# Sheet1.net
KiCad netlist of a schematic drawn in Altium Designer
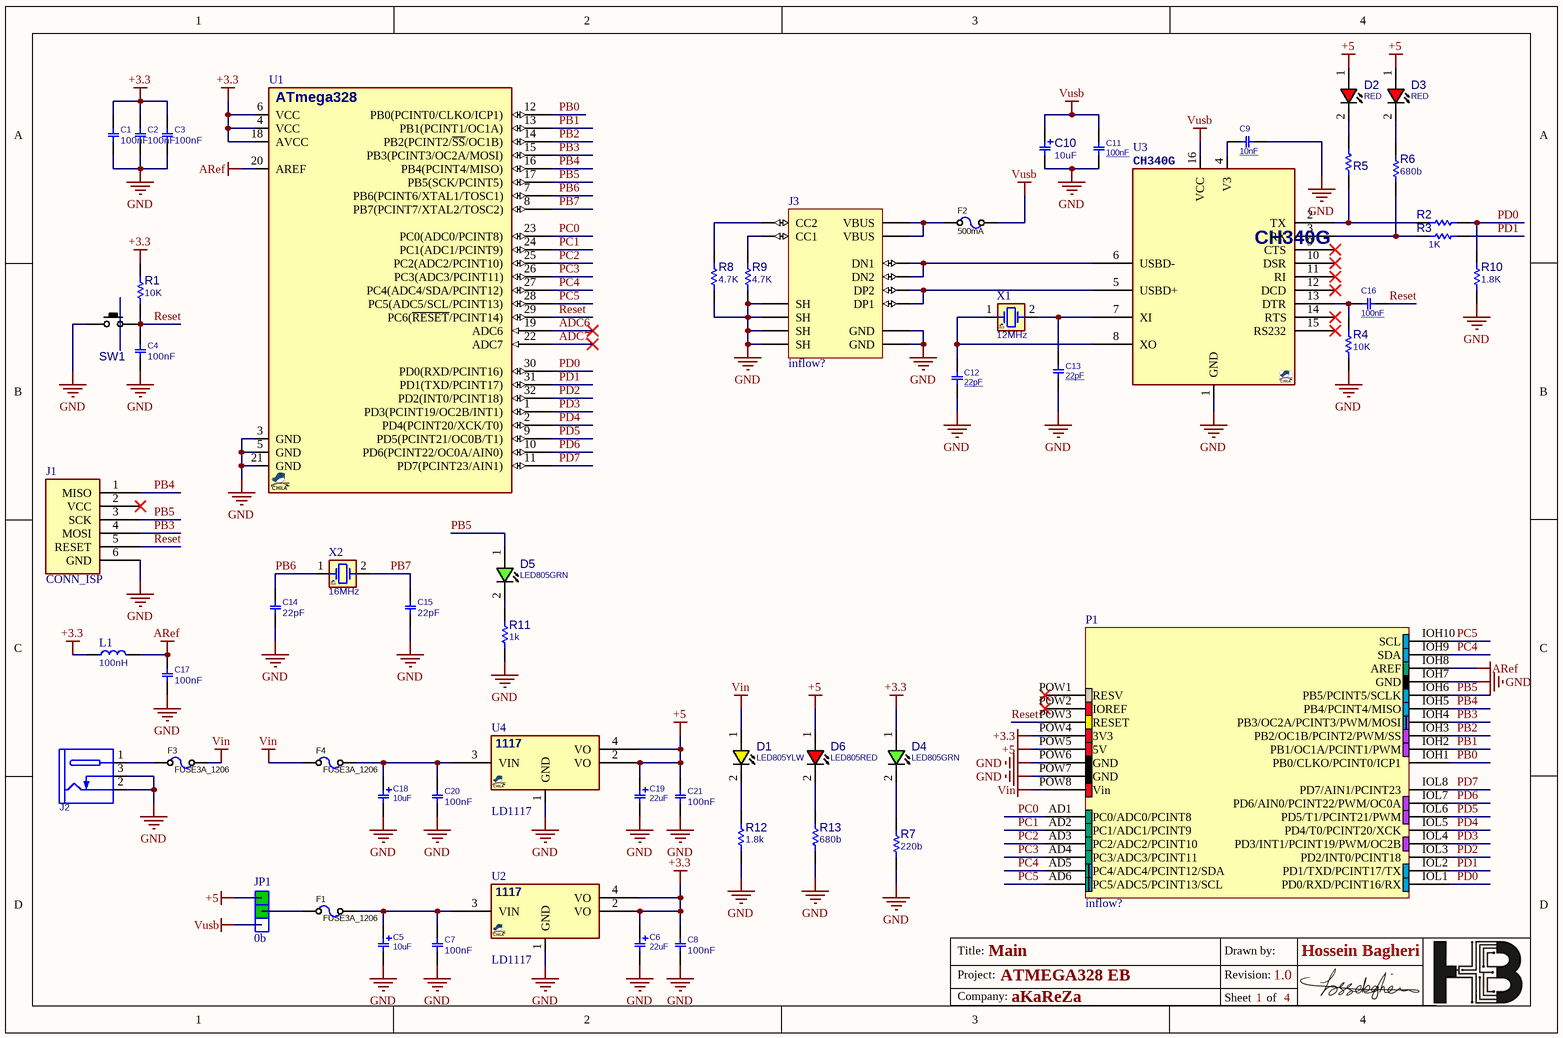
[diagram p0: Sheet1.SchDoc]

(export (version "E")
  (design (tool "Eeschema 10.0.6"))
  (components
    (comp (ref "C1")
      (value "100nF")
      (footprint "C0805")
      (description "CAP, MLCC")
      (fields (field (name "MANF_P#") "MANF_PART#"))
      (libsource (lib "Chila_PCB") (part "CAP_SMD_MLCC_0805"))
    )
    (comp (ref "C2")
      (value "100nF")
      (footprint "C0805")
      (description "CAP, MLCC")
      (fields (field (name "MANF_P#") "MANF_PART#"))
      (libsource (lib "Chila_PCB") (part "CAP_SMD_MLCC_0805"))
    )
    (comp (ref "C3")
      (value "100nF")
      (footprint "C0805")
      (description "CAP, MLCC")
      (fields (field (name "MANF_P#") "MANF_PART#"))
      (libsource (lib "Chila_PCB") (part "CAP_SMD_MLCC_0805"))
    )
    (comp (ref "C4")
      (value "100nF")
      (footprint "C0805")
      (description "CAP, MLCC")
      (fields (field (name "MANF_P#") "MANF_PART#"))
      (libsource (lib "Chila_PCB") (part "CAP_SMD_MLCC_0805"))
    )
    (comp (ref "C5")
      (value "10uF")
      (footprint "C_TN_2012")
      (description "CAP, SMD, TAN")
      (fields (field (name "MANF") "VISHAY") (field (name "MANF_P#") "T55A106M6R3C0300"))
      (libsource (lib "Chila_PCB") (part "CAP_SMD_TAN"))
    )
    (comp (ref "C6")
      (value "22uF")
      (footprint "C_TN_2012")
      (description "CAP, SMD, TAN")
      (fields (field (name "MANF") "VISHAY") (field (name "MANF_P#") "T55A106M6R3C0300"))
      (libsource (lib "Chila_PCB") (part "CAP_SMD_TAN"))
    )
    (comp (ref "C7")
      (value "100nF")
      (footprint "C1206")
      (description "CAP, MLCC")
      (fields (field (name "MANF_P#") "MANF_PART#"))
      (libsource (lib "Chila_PCB") (part "CAP_SMD_MLCC_1206"))
    )
    (comp (ref "C8")
      (value "100nF")
      (footprint "C1206")
      (description "CAP, MLCC")
      (fields (field (name "MANF_P#") "MANF_PART#"))
      (libsource (lib "Chila_PCB") (part "CAP_SMD_MLCC_1206"))
    )
    (comp (ref "C9")
      (value "10nF")
      (footprint "C1206")
      (description "CAP, FILM, 680nF, 16V, Acryl, 20%, 1206")
      (fields (field (name "MANF") "Murata"))
      (libsource (lib "Chila_PCB") (part "CAP_SMD_FILM"))
    )
    (comp (ref "C10")
      (value "10uF")
      (footprint "C_EL_D4L5")
      (description "CAP, SMD, ELEC,")
      (fields (field (name "MANF_P#") "MANF_PART#") (field (name "MANF") "MANF"))
      (libsource (lib "Chila_PCB") (part "CAP_SMD_EL"))
    )
    (comp (ref "C11")
      (value "100nF")
      (footprint "C1206")
      (description "CAP, FILM, 680nF, 16V, Acryl, 20%, 1206")
      (fields (field (name "MANF") "Murata"))
      (libsource (lib "Chila_PCB") (part "CAP_SMD_FILM"))
    )
    (comp (ref "C12")
      (value "22pF")
      (footprint "C1206")
      (description "CAP, FILM, 680nF, 16V, Acryl, 20%, 1206")
      (fields (field (name "MANF") "Murata"))
      (libsource (lib "Chila_PCB") (part "CAP_SMD_FILM"))
    )
    (comp (ref "C13")
      (value "22pF")
      (footprint "C1206")
      (description "CAP, FILM, 680nF, 16V, Acryl, 20%, 1206")
      (fields (field (name "MANF") "Murata"))
      (libsource (lib "Chila_PCB") (part "CAP_SMD_FILM"))
    )
    (comp (ref "C14")
      (value "22pF")
      (footprint "C0805")
      (description "CAP, MLCC")
      (fields (field (name "MANF_P#") "MANF_PART#"))
      (libsource (lib "Chila_PCB") (part "CAP_SMD_MLCC_0805"))
    )
    (comp (ref "C15")
      (value "22pF")
      (footprint "C0805")
      (description "CAP, MLCC")
      (fields (field (name "MANF_P#") "MANF_PART#"))
      (libsource (lib "Chila_PCB") (part "CAP_SMD_MLCC_0805"))
    )
    (comp (ref "C16")
      (value "100nF")
      (footprint "C1206")
      (description "CAP, FILM, 680nF, 16V, Acryl, 20%, 1206")
      (fields (field (name "MANF") "Murata"))
      (libsource (lib "Chila_PCB") (part "CAP_SMD_FILM"))
    )
    (comp (ref "C17")
      (value "100nF")
      (footprint "C0805")
      (description "CAP, MLCC")
      (fields (field (name "MANF_P#") "MANF_PART#"))
      (libsource (lib "Chila_PCB") (part "CAP_SMD_MLCC_0805"))
    )
    (comp (ref "C18")
      (value "10uF")
      (footprint "C_TN_2012")
      (description "CAP, SMD, TAN")
      (fields (field (name "MANF") "VISHAY") (field (name "MANF_P#") "T55A106M6R3C0300"))
      (libsource (lib "Chila_PCB") (part "CAP_SMD_TAN"))
    )
    (comp (ref "C19")
      (value "22uF")
      (footprint "C_TN_2012")
      (description "CAP, SMD, TAN")
      (fields (field (name "MANF") "VISHAY") (field (name "MANF_P#") "T55A106M6R3C0300"))
      (libsource (lib "Chila_PCB") (part "CAP_SMD_TAN"))
    )
    (comp (ref "C20")
      (value "100nF")
      (footprint "C1206")
      (description "CAP, MLCC")
      (fields (field (name "MANF_P#") "MANF_PART#"))
      (libsource (lib "Chila_PCB") (part "CAP_SMD_MLCC_1206"))
    )
    (comp (ref "C21")
      (value "100nF")
      (footprint "C1206")
      (description "CAP, MLCC")
      (fields (field (name "MANF_P#") "MANF_PART#"))
      (libsource (lib "Chila_PCB") (part "CAP_SMD_MLCC_1206"))
    )
    (comp (ref "D1")
      (value "LED805YLW")
      (footprint "LED0805YLW")
      (description "LED, SMD, 0805, YELLOW")
      (fields (field (name "MANF") "MANF") (field (name "MANF_P#") "MANF_PART#"))
      (libsource (lib "Chila_PCB") (part "LED_SMD_0805_YLW"))
    )
    (comp (ref "D2")
      (value "RED")
      (footprint "LED0805RED")
      (description "LED, SMD, 0805, RED")
      (fields (field (name "MANF") "MANF") (field (name "MANF_P#") "MANF_PART#"))
      (libsource (lib "Chila_PCB") (part "LED_SMD_0805_RED"))
    )
    (comp (ref "D3")
      (value "RED")
      (footprint "LED0805RED")
      (description "LED, SMD, 0805, RED")
      (fields (field (name "MANF") "MANF") (field (name "MANF_P#") "MANF_PART#"))
      (libsource (lib "Chila_PCB") (part "LED_SMD_0805_RED"))
    )
    (comp (ref "D4")
      (value "LED805GRN")
      (footprint "LED0805GRN")
      (description "LED, SMD, 0805, GREEN")
      (libsource (lib "Chila_PCB") (part "LED_SMD_0805_GRN"))
    )
    (comp (ref "D5")
      (value "LED805GRN")
      (footprint "LED0805GRN")
      (description "LED, SMD, 0805, GREEN")
      (libsource (lib "Chila_PCB") (part "LED_SMD_0805_GRN"))
    )
    (comp (ref "D6")
      (value "LED805RED")
      (footprint "LED0805RED")
      (description "LED, SMD, 0805, RED")
      (fields (field (name "MANF") "MANF") (field (name "MANF_P#") "MANF_PART#"))
      (libsource (lib "Chila_PCB") (part "LED_SMD_0805_RED"))
    )
    (comp (ref "F1")
      (value "FUSE3A_1206")
      (footprint "F1206")
      (description "Fuse, 3A, 32VDC, 1206, SMD, Slow Blow")
      (fields (field (name "MANF") "Bourns") (field (name "MANF_P#") "SF-1206SP300-2"))
      (libsource (lib "Chila_PCB") (part "FUSE_3A_1206_SLOW"))
    )
    (comp (ref "F2")
      (value "500mA")
      (footprint "F1206")
      (description "Fuse, 3A, 32VDC, 1206, SMD, Slow Blow")
      (fields (field (name "MANF") "Bourns") (field (name "MANF_P#") "SF-1206SP300-2"))
      (libsource (lib "Chila_PCB") (part "FUSE_3A_1206_SLOW"))
    )
    (comp (ref "F3")
      (value "FUSE3A_1206")
      (footprint "F1206")
      (description "Fuse, 3A, 32VDC, 1206, SMD, Slow Blow")
      (fields (field (name "MANF") "Bourns") (field (name "MANF_P#") "SF-1206SP300-2"))
      (libsource (lib "Chila_PCB") (part "FUSE_3A_1206_SLOW"))
    )
    (comp (ref "F4")
      (value "FUSE3A_1206")
      (footprint "F1206")
      (description "Fuse, 3A, 32VDC, 1206, SMD, Slow Blow")
      (fields (field (name "MANF") "Bourns") (field (name "MANF_P#") "SF-1206SP300-2"))
      (libsource (lib "Chila_PCB") (part "FUSE_3A_1206_SLOW"))
    )
    (comp (ref "J1")
      (value "CONN_ISP")
      (footprint "IDC_2X3")
      (description "CONN, ISP, AVR , HEADER BOX")
      (libsource (lib "Chila_PCB") (part "CONN_AVR_ISP_IDC6"))
    )
    (comp (ref "J2")
      (value "DC_POWER_JACK")
      (footprint "JAC_PWR2")
      (description "CONN, PWR JACK DC, PLUG DIAM 2.0MM RA THD")
      (fields
        (field (name "MANF") "CUI STACK")
        (field (name "MANF_P#") "PJ-202A, PJ-002AH, PJ-102AH, KLDX-0202")
      )
      (libsource (lib "Chila_PCB") (part "CONN_PWR_JACKR2"))
    )
    (comp (ref "J3")
      (value "12b")
      (footprint "HRO_TYPE-C-31-M-12 - Extended")
      (description "USB C Female Connector")
      (fields (field (name "INFLOW") "inflow?") (field (name "VALIDATION") "Valid"))
      (libsource (lib "aKaReZa") (part "Con_USB_C"))
    )
    (comp (ref "JP1")
      (value "0b")
      (footprint "jumper selector")
      (description "Jumper Selector")
      (fields (field (name "VALIDATION") "NT"))
      (libsource (lib "aKaReZa") (part "SW_Other_JSelector_Dip"))
    )
    (comp (ref "L1")
      (value "100nH")
      (footprint "L0805")
      (description "INDUCTOR, SMD")
      (fields (field (name "MANF") "EPCOS / TDK") (field (name "MANF_P#") "B82498F3331J"))
      (libsource (lib "Chila_PCB") (part "IND_SMD_330nH_0.2A"))
    )
    (comp (ref "P1")
      (value "UNO")
      (footprint "ARDUINO_UNO_CONNECTOR")
      (description "Arduino UNO Connector")
      (fields (field (name "INFLOW") "inflow?") (field (name "VALIDATION") "NT"))
      (libsource (lib "aKaReZa") (part "Con_Arduino_UNO_Con"))
    )
    (comp (ref "R1")
      (value "10K")
      (footprint "R0805")
      (description "RESISTOR, SMD")
      (libsource (lib "Chila_PCB") (part "RES_SMD_0805"))
    )
    (comp (ref "R2")
      (value "1K")
      (footprint "R0805")
      (description "RESISTOR, SMD")
      (libsource (lib "Chila_PCB") (part "RES_SMD_0805"))
    )
    (comp (ref "R3")
      (value "1K")
      (footprint "R0805")
      (description "RESISTOR, SMD")
      (libsource (lib "Chila_PCB") (part "RES_SMD_0805"))
    )
    (comp (ref "R4")
      (value "10K")
      (footprint "R0805")
      (description "RESISTOR, SMD")
      (libsource (lib "Chila_PCB") (part "RES_SMD_0805"))
    )
    (comp (ref "R5")
      (value "680b")
      (footprint "R0805")
      (description "RESISTOR, SMD")
      (libsource (lib "Chila_PCB") (part "RES_SMD_0805"))
    )
    (comp (ref "R6")
      (value "680b")
      (footprint "R0805")
      (description "RESISTOR, SMD")
      (libsource (lib "Chila_PCB") (part "RES_SMD_0805"))
    )
    (comp (ref "R7")
      (value "220b")
      (footprint "R0805")
      (description "RESISTOR, SMD")
      (libsource (lib "Chila_PCB") (part "RES_SMD_0805"))
    )
    (comp (ref "R8")
      (value "4.7K")
      (footprint "R0805")
      (description "RESISTOR, SMD")
      (libsource (lib "Chila_PCB") (part "RES_SMD_0805"))
    )
    (comp (ref "R9")
      (value "4.7K")
      (footprint "R0805")
      (description "RESISTOR, SMD")
      (libsource (lib "Chila_PCB") (part "RES_SMD_0805"))
    )
    (comp (ref "R10")
      (value "1.8K")
      (footprint "R0805")
      (description "RESISTOR, SMD")
      (libsource (lib "Chila_PCB") (part "RES_SMD_0805"))
    )
    (comp (ref "R11")
      (value "1k")
      (footprint "R0805")
      (description "RESISTOR, SMD")
      (libsource (lib "Chila_PCB") (part "RES_SMD_0805"))
    )
    (comp (ref "R12")
      (value "1.8k")
      (footprint "R0805")
      (description "RESISTOR, SMD")
      (libsource (lib "Chila_PCB") (part "RES_SMD_0805"))
    )
    (comp (ref "R13")
      (value "680b")
      (footprint "R0805")
      (description "RESISTOR, SMD")
      (libsource (lib "Chila_PCB") (part "RES_SMD_0805"))
    )
    (comp (ref "SW1")
      (value "PUSHBUTTON")
      (footprint "SWPBS_SPST_6X3X2")
      (description "SWITCH, PUSH BUTTON, TACTILE, SMD, SPST, 6X3.5X2.5mm")
      (fields (field (name "MANF") "C&K") (field (name "MANF_P#") "RS-282G05A3-SM RT"))
      (libsource (lib "Chila_PCB") (part "SWPBS_SPST_6X3X2_RS282"))
    )
    (comp (ref "U1")
      (value "ATMEGA328")
      (footprint "QFG80_32")
      (description "MCU, AVR, 8-Bit, 16KB, 1KB RAM, 20MHz")
      (fields (field (name "MANF_P#") "ATMEGA328-AU") (field (name "MANF") "ATMEL/MICROCHIP"))
      (libsource (lib "Chila_PCB") (part "ATMEGA328_QFP32"))
    )
    (comp (ref "U2")
      (value "LD1117")
      (footprint "SOT223_4")
      (description "REG, Linear, LDO1V, 0.8A, SOT-223")
      (fields
        (field (name "MANF_P#") "LD1117, LM1117, AMS1117, TLV1117, REG1117, NCP1117, LT1117, SPX1117")
        (field (name "MANF") "TI, ON, ST")
      )
      (libsource (lib "Chila_PCB") (part "VREG_1117_SOT223"))
    )
    (comp (ref "U3")
      (value "CH340G")
      (footprint "SO_16")
      (description "USB-UART")
      (libsource (lib "Chila_PCB") (part "CH340G_SOP16"))
    )
    (comp (ref "U4")
      (value "LD1117")
      (footprint "SOT223_4")
      (description "REG, Linear, LDO1V, 0.8A, SOT-223")
      (fields
        (field (name "MANF_P#") "LD1117, LM1117, AMS1117, TLV1117, REG1117, NCP1117, LT1117, SPX1117")
        (field (name "MANF") "TI, ON, ST")
      )
      (libsource (lib "Chila_PCB") (part "VREG_1117_SOT223"))
    )
    (comp (ref "X1")
      (value "12MHz")
      (footprint "XTL_2_11X5")
      (description "Crystal MOST POPULAR ABL HC49 PACKAGE")
      (fields (field (name "MANF") "ABRACON") (field (name "MANF_P#") "ABLS-8.000MHZ-B4-T"))
      (libsource (lib "Chila_PCB") (part "XTL_2_HC49_8MHz_SMD"))
    )
    (comp (ref "X2")
      (value "16MHz")
      (footprint "XTL_2_11X5")
      (description "Crystal MOST POPULAR ABL HC49 PACKAGE")
      (libsource (lib "Chila_PCB") (part "XTL_2_HC49_SMD"))
    )
  )
  (nets
    (net (code "1") (name "+3.3") (class "Default")
      (node (ref "C1") (pin "2") (pinfunction "2_2") (pintype "passive"))
      (node (ref "C2") (pin "2") (pinfunction "2_2") (pintype "passive"))
      (node (ref "C3") (pin "2") (pinfunction "2_2") (pintype "passive"))
      (node (ref "C6") (pin "1") (pinfunction "1_1") (pintype "passive"))
      (node (ref "C8") (pin "2") (pinfunction "2_2") (pintype "passive"))
      (node (ref "D4") (pin "1") (pinfunction "ANODE_1") (pintype "passive"))
      (node (ref "L1") (pin "1") (pinfunction "1_1") (pintype "passive"))
      (node (ref "P1") (pin "POW4") (pinfunction "3V3_POW4") (pintype "passive"))
      (node (ref "R1") (pin "1") (pinfunction "1_1") (pintype "passive"))
      (node (ref "U1") (pin "18") (pinfunction "AVCC_18") (pintype "power_in"))
      (node (ref "U1") (pin "4") (pinfunction "VCC_4") (pintype "power_in"))
      (node (ref "U1") (pin "6") (pinfunction "VCC_6") (pintype "power_in"))
      (node (ref "U2") (pin "2") (pinfunction "VO_2") (pintype "passive"))
      (node (ref "U2") (pin "4") (pinfunction "VO_4") (pintype "passive"))
    )
    (net (code "2") (name "+5") (class "Default")
      (node (ref "C19") (pin "1") (pinfunction "1_1") (pintype "passive"))
      (node (ref "C21") (pin "2") (pinfunction "2_2") (pintype "passive"))
      (node (ref "D2") (pin "1") (pinfunction "ANODE_1") (pintype "passive"))
      (node (ref "D3") (pin "1") (pinfunction "ANODE_1") (pintype "passive"))
      (node (ref "D6") (pin "1") (pinfunction "ANODE_1") (pintype "passive"))
      (node (ref "JP1") (pin "1") (pinfunction "1_1") (pintype "passive"))
      (node (ref "P1") (pin "POW5") (pinfunction "5V_POW5") (pintype "passive"))
      (node (ref "U4") (pin "2") (pinfunction "VO_2") (pintype "passive"))
      (node (ref "U4") (pin "4") (pinfunction "VO_4") (pintype "passive"))
    )
    (net (code "3") (name "/ADC6") (class "Default")
      (node (ref "U1") (pin "19") (pinfunction "ADC6_19") (pintype "input+no_connect"))
    )
    (net (code "4") (name "/ADC7") (class "Default")
      (node (ref "U1") (pin "22") (pinfunction "ADC7_22") (pintype "input+no_connect"))
    )
    (net (code "5") (name "/PB0") (class "Default")
      (node (ref "P1") (pin "IOH1") (pinfunction "PB0/CLKO/PCINT0/ICP1_IOH1") (pintype "passive"))
      (node (ref "U1") (pin "12") (pinfunction "PB0(PCINT0/CLKO/ICP1)_12") (pintype "bidirectional"))
    )
    (net (code "6") (name "/PB1") (class "Default")
      (node (ref "P1") (pin "IOH2") (pinfunction "PB1/OC1A/PCINT1/PWM_IOH2") (pintype "passive"))
      (node (ref "U1") (pin "13") (pinfunction "PB1(PCINT1/OC1A)_13") (pintype "bidirectional"))
    )
    (net (code "7") (name "/PB2") (class "Default")
      (node (ref "P1") (pin "IOH3") (pinfunction "PB2/OC1B/PCINT2/PWM/SS_IOH3") (pintype "passive"))
      (node (ref "U1") (pin "14") (pinfunction "PB2(PCINT2/~{SS}/OC1B)_14") (pintype "bidirectional"))
    )
    (net (code "8") (name "/PB3") (class "Default")
      (node (ref "J1") (pin "4") (pinfunction "MOSI_4") (pintype "passive"))
      (node (ref "P1") (pin "IOH4") (pinfunction "PB3/OC2A/PCINT3/PWM/MOSI_IOH4") (pintype "passive"))
      (node (ref "U1") (pin "15") (pinfunction "PB3(PCINT3/OC2A/MOSI)_15") (pintype "bidirectional"))
    )
    (net (code "9") (name "/PB4") (class "Default")
      (node (ref "J1") (pin "1") (pinfunction "MISO_1") (pintype "passive"))
      (node (ref "P1") (pin "IOH5") (pinfunction "PB4/PCINT4/MISO_IOH5") (pintype "passive"))
      (node (ref "U1") (pin "16") (pinfunction "PB4(PCINT4/MISO)_16") (pintype "bidirectional"))
    )
    (net (code "10") (name "/PB5") (class "Default")
      (node (ref "D5") (pin "1") (pinfunction "ANODE_1") (pintype "passive"))
      (node (ref "J1") (pin "3") (pinfunction "SCK_3") (pintype "passive"))
      (node (ref "P1") (pin "IOH6") (pinfunction "PB5/PCINT5/SCLK_IOH6") (pintype "passive"))
      (node (ref "U1") (pin "17") (pinfunction "PB5(SCK/PCINT5)_17") (pintype "bidirectional"))
    )
    (net (code "11") (name "/PB6") (class "Default")
      (node (ref "C14") (pin "2") (pinfunction "2_2") (pintype "passive"))
      (node (ref "U1") (pin "7") (pinfunction "PB6(PCINT6/XTAL1/TOSC1)_7") (pintype "bidirectional"))
      (node (ref "X2") (pin "1") (pinfunction "OSC1_1") (pintype "passive"))
    )
    (net (code "12") (name "/PB7") (class "Default")
      (node (ref "C15") (pin "2") (pinfunction "2_2") (pintype "passive"))
      (node (ref "U1") (pin "8") (pinfunction "PB7(PCINT7/XTAL2/TOSC2)_8") (pintype "bidirectional"))
      (node (ref "X2") (pin "2") (pinfunction "OSC2_2") (pintype "passive"))
    )
    (net (code "13") (name "/PC0") (class "Default")
      (node (ref "P1") (pin "AD1") (pinfunction "PC0/ADC0/PCINT8_AD1") (pintype "passive"))
      (node (ref "U1") (pin "23") (pinfunction "PC0(ADC0/PCINT8)_23") (pintype "bidirectional"))
    )
    (net (code "14") (name "/PC1") (class "Default")
      (node (ref "P1") (pin "AD2") (pinfunction "PC1/ADC1/PCINT9_AD2") (pintype "passive"))
      (node (ref "U1") (pin "24") (pinfunction "PC1(ADC1/PCINT9)_24") (pintype "bidirectional"))
    )
    (net (code "15") (name "/PC2") (class "Default")
      (node (ref "P1") (pin "AD3") (pinfunction "PC2/ADC2/PCINT10_AD3") (pintype "passive"))
      (node (ref "U1") (pin "25") (pinfunction "PC2(ADC2/PCINT10)_25") (pintype "bidirectional"))
    )
    (net (code "16") (name "/PC3") (class "Default")
      (node (ref "P1") (pin "AD4") (pinfunction "PC3/ADC3/PCINT11_AD4") (pintype "passive"))
      (node (ref "U1") (pin "26") (pinfunction "PC3(ADC3/PCINT11)_26") (pintype "bidirectional"))
    )
    (net (code "17") (name "/PC4") (class "Default")
      (node (ref "P1") (pin "AD5") (pinfunction "PC4/ADC4/PCINT12/SDA_AD5") (pintype "passive"))
      (node (ref "P1") (pin "IOH9") (pinfunction "SDA_IOH9") (pintype "passive"))
      (node (ref "U1") (pin "27") (pinfunction "PC4(ADC4/SDA/PCINT12)_27") (pintype "bidirectional"))
    )
    (net (code "18") (name "/PC5") (class "Default")
      (node (ref "P1") (pin "AD6") (pinfunction "PC5/ADC5/PCINT13/SCL_AD6") (pintype "passive"))
      (node (ref "P1") (pin "IOH10") (pinfunction "SCL_IOH10") (pintype "passive"))
      (node (ref "U1") (pin "28") (pinfunction "PC5(ADC5/SCL/PCINT13)_28") (pintype "bidirectional"))
    )
    (net (code "19") (name "/PD0") (class "Default")
      (node (ref "P1") (pin "IOL1") (pinfunction "PD0/RXD/PCINT16/RX_IOL1") (pintype "passive"))
      (node (ref "R10") (pin "2") (pinfunction "2_2") (pintype "passive"))
      (node (ref "R2") (pin "2") (pinfunction "2_2") (pintype "passive"))
      (node (ref "U1") (pin "30") (pinfunction "PD0(RXD/PCINT16)_30") (pintype "bidirectional"))
    )
    (net (code "20") (name "/PD1") (class "Default")
      (node (ref "P1") (pin "IOL2") (pinfunction "PD1/TXD/PCINT17/TX_IOL2") (pintype "passive"))
      (node (ref "R3") (pin "2") (pinfunction "2_2") (pintype "passive"))
      (node (ref "U1") (pin "31") (pinfunction "PD1(TXD/PCINT17)_31") (pintype "bidirectional"))
    )
    (net (code "21") (name "/PD2") (class "Default")
      (node (ref "P1") (pin "IOL3") (pinfunction "PD2/INT0/PCINT18_IOL3") (pintype "passive"))
      (node (ref "U1") (pin "32") (pinfunction "PD2(INT0/PCINT18)_32") (pintype "bidirectional"))
    )
    (net (code "22") (name "/PD3") (class "Default")
      (node (ref "P1") (pin "IOL4") (pinfunction "PD3/INT1/PCINT19/PWM/OC2B_IOL4") (pintype "passive"))
      (node (ref "U1") (pin "1") (pinfunction "PD3(PCINT19/OC2B/INT1)_1") (pintype "bidirectional"))
    )
    (net (code "23") (name "/PD4") (class "Default")
      (node (ref "P1") (pin "IOL5") (pinfunction "PD4/T0/PCINT20/XCK_IOL5") (pintype "passive"))
      (node (ref "U1") (pin "2") (pinfunction "PD4(PCINT20/XCK/T0)_2") (pintype "bidirectional"))
    )
    (net (code "24") (name "/PD5") (class "Default")
      (node (ref "P1") (pin "IOL6") (pinfunction "PD5/T1/PCINT21/PWM_IOL6") (pintype "passive"))
      (node (ref "U1") (pin "9") (pinfunction "PD5(PCINT21/OC0B/T1)_9") (pintype "bidirectional"))
    )
    (net (code "25") (name "/PD6") (class "Default")
      (node (ref "P1") (pin "IOL7") (pinfunction "PD6/AIN0/PCINT22/PWM/OC0A_IOL7") (pintype "passive"))
      (node (ref "U1") (pin "10") (pinfunction "PD6(PCINT22/OC0A/AIN0)_10") (pintype "bidirectional"))
    )
    (net (code "26") (name "/PD7") (class "Default")
      (node (ref "P1") (pin "IOL8") (pinfunction "PD7/AIN1/PCINT23_IOL8") (pintype "passive"))
      (node (ref "U1") (pin "11") (pinfunction "PD7(PCINT23/AIN1)_11") (pintype "bidirectional"))
    )
    (net (code "27") (name "/Reset") (class "Default")
      (node (ref "C16") (pin "1") (pinfunction "1_1") (pintype "passive"))
      (node (ref "C4") (pin "2") (pinfunction "2_2") (pintype "passive"))
      (node (ref "J1") (pin "5") (pinfunction "RESET_5") (pintype "passive"))
      (node (ref "P1") (pin "POW3") (pinfunction "RESET_POW3") (pintype "passive"))
      (node (ref "R1") (pin "2") (pinfunction "2_2") (pintype "passive"))
      (node (ref "SW1") (pin "2") (pinfunction "P3_2") (pintype "passive"))
      (node (ref "U1") (pin "29") (pinfunction "PC6(~{RESET}/PCINT14)_29") (pintype "bidirectional"))
    )
    (net (code "28") (name "ARef") (class "Default")
      (node (ref "C17") (pin "2") (pinfunction "2_2") (pintype "passive"))
      (node (ref "L1") (pin "2") (pinfunction "2_2") (pintype "passive"))
      (node (ref "P1") (pin "IOH8") (pinfunction "AREF_IOH8") (pintype "passive"))
      (node (ref "U1") (pin "20") (pinfunction "AREF_20") (pintype "passive"))
    )
    (net (code "29") (name "GND") (class "Default")
      (node (ref "C1") (pin "1") (pinfunction "1_1") (pintype "passive"))
      (node (ref "C10") (pin "2") (pinfunction "2_2") (pintype "passive"))
      (node (ref "C11") (pin "1") (pinfunction "1_1") (pintype "passive"))
      (node (ref "C12") (pin "1") (pinfunction "1_1") (pintype "passive"))
      (node (ref "C13") (pin "1") (pinfunction "1_1") (pintype "passive"))
      (node (ref "C14") (pin "1") (pinfunction "1_1") (pintype "passive"))
      (node (ref "C15") (pin "1") (pinfunction "1_1") (pintype "passive"))
      (node (ref "C17") (pin "1") (pinfunction "1_1") (pintype "passive"))
      (node (ref "C18") (pin "2") (pinfunction "2_2") (pintype "passive"))
      (node (ref "C19") (pin "2") (pinfunction "2_2") (pintype "passive"))
      (node (ref "C2") (pin "1") (pinfunction "1_1") (pintype "passive"))
      (node (ref "C20") (pin "1") (pinfunction "1_1") (pintype "passive"))
      (node (ref "C21") (pin "1") (pinfunction "1_1") (pintype "passive"))
      (node (ref "C3") (pin "1") (pinfunction "1_1") (pintype "passive"))
      (node (ref "C4") (pin "1") (pinfunction "1_1") (pintype "passive"))
      (node (ref "C5") (pin "2") (pinfunction "2_2") (pintype "passive"))
      (node (ref "C6") (pin "2") (pinfunction "2_2") (pintype "passive"))
      (node (ref "C7") (pin "1") (pinfunction "1_1") (pintype "passive"))
      (node (ref "C8") (pin "1") (pinfunction "1_1") (pintype "passive"))
      (node (ref "C9") (pin "1") (pinfunction "1_1") (pintype "passive"))
      (node (ref "J1") (pin "6") (pinfunction "GND_6") (pintype "passive"))
      (node (ref "J2") (pin "2") (pinfunction "SLEEVE_2") (pintype "power_in"))
      (node (ref "J2") (pin "3") (pinfunction "INSERTION_DET_3") (pintype "power_in"))
      (node (ref "J3") (pin "A1_B12") (pinfunction "GND_A1_B12") (pintype "power_in"))
      (node (ref "J3") (pin "B1_A12") (pinfunction "GND_B1_A12") (pintype "power_in"))
      (node (ref "J3") (pin "S1") (pinfunction "SH_S1") (pintype "passive"))
      (node (ref "J3") (pin "S2") (pinfunction "SH_S2") (pintype "passive"))
      (node (ref "J3") (pin "S3") (pinfunction "SH_S3") (pintype "passive"))
      (node (ref "J3") (pin "S4") (pinfunction "SH_S4") (pintype "passive"))
      (node (ref "P1") (pin "IOH7") (pinfunction "GND_IOH7") (pintype "passive"))
      (node (ref "P1") (pin "POW6") (pinfunction "GND_POW6") (pintype "passive"))
      (node (ref "P1") (pin "POW7") (pinfunction "GND_POW7") (pintype "passive"))
      (node (ref "R10") (pin "1") (pinfunction "1_1") (pintype "passive"))
      (node (ref "R11") (pin "1") (pinfunction "1_1") (pintype "passive"))
      (node (ref "R12") (pin "1") (pinfunction "1_1") (pintype "passive"))
      (node (ref "R13") (pin "1") (pinfunction "1_1") (pintype "passive"))
      (node (ref "R4") (pin "1") (pinfunction "1_1") (pintype "passive"))
      (node (ref "R7") (pin "1") (pinfunction "1_1") (pintype "passive"))
      (node (ref "R8") (pin "1") (pinfunction "1_1") (pintype "passive"))
      (node (ref "R9") (pin "1") (pinfunction "1_1") (pintype "passive"))
      (node (ref "SW1") (pin "1") (pinfunction "P1_1") (pintype "passive"))
      (node (ref "U1") (pin "21") (pinfunction "GND_21") (pintype "power_in"))
      (node (ref "U1") (pin "3") (pinfunction "GND_3") (pintype "power_in"))
      (node (ref "U1") (pin "5") (pinfunction "GND_5") (pintype "power_in"))
      (node (ref "U2") (pin "1") (pinfunction "GND_1") (pintype "passive"))
      (node (ref "U3") (pin "1") (pinfunction "GND_1") (pintype "passive"))
      (node (ref "U4") (pin "1") (pinfunction "GND_1") (pintype "passive"))
    )
    (net (code "30") (name "Net-(D1-CATHODE)") (class "Default")
      (node (ref "D1") (pin "2") (pinfunction "CATHODE_2") (pintype "passive"))
      (node (ref "R12") (pin "2") (pinfunction "2_2") (pintype "passive"))
    )
    (net (code "31") (name "Net-(D2-CATHODE)") (class "Default")
      (node (ref "D2") (pin "2") (pinfunction "CATHODE_2") (pintype "passive"))
      (node (ref "R5") (pin "2") (pinfunction "2_2") (pintype "passive"))
    )
    (net (code "32") (name "Net-(D3-CATHODE)") (class "Default")
      (node (ref "D3") (pin "2") (pinfunction "CATHODE_2") (pintype "passive"))
      (node (ref "R6") (pin "2") (pinfunction "2_2") (pintype "passive"))
    )
    (net (code "33") (name "Net-(D4-CATHODE)") (class "Default")
      (node (ref "D4") (pin "2") (pinfunction "CATHODE_2") (pintype "passive"))
      (node (ref "R7") (pin "2") (pinfunction "2_2") (pintype "passive"))
    )
    (net (code "34") (name "Net-(D5-CATHODE)") (class "Default")
      (node (ref "D5") (pin "2") (pinfunction "CATHODE_2") (pintype "passive"))
      (node (ref "R11") (pin "2") (pinfunction "2_2") (pintype "passive"))
    )
    (net (code "35") (name "Net-(D6-CATHODE)") (class "Default")
      (node (ref "D6") (pin "2") (pinfunction "CATHODE_2") (pintype "passive"))
      (node (ref "R13") (pin "2") (pinfunction "2_2") (pintype "passive"))
    )
    (net (code "36") (name "Net-(F1-Pad1)") (class "Default")
      (node (ref "F1") (pin "1") (pinfunction "1_1") (pintype "passive"))
      (node (ref "JP1") (pin "2") (pinfunction "2_2") (pintype "passive"))
    )
    (net (code "37") (name "Net-(F2-Pad1)") (class "Default")
      (node (ref "F2") (pin "1") (pinfunction "1_1") (pintype "passive"))
      (node (ref "J3") (pin "A4_B9") (pinfunction "VBUS_A4_B9") (pintype "power_in"))
      (node (ref "J3") (pin "B4_A9") (pinfunction "VBUS_B4_A9") (pintype "power_in"))
    )
    (net (code "38") (name "Net-(J2-TIP)") (class "Default")
      (node (ref "F3") (pin "1") (pinfunction "1_1") (pintype "passive"))
      (node (ref "J2") (pin "1") (pinfunction "TIP_1") (pintype "power_in"))
    )
    (net (code "39") (name "Net-(J3-CC1)") (class "Default")
      (node (ref "J3") (pin "A5") (pinfunction "CC1_A5") (pintype "bidirectional"))
      (node (ref "R9") (pin "2") (pinfunction "2_2") (pintype "passive"))
    )
    (net (code "40") (name "Net-(J3-CC2)") (class "Default")
      (node (ref "J3") (pin "B5") (pinfunction "CC2_B5") (pintype "bidirectional"))
      (node (ref "R8") (pin "2") (pinfunction "2_2") (pintype "passive"))
    )
    (net (code "41") (name "Net-(J3-DN1)") (class "Default")
      (node (ref "J3") (pin "A7") (pinfunction "DN1_A7") (pintype "bidirectional"))
      (node (ref "J3") (pin "B7") (pinfunction "DN2_B7") (pintype "bidirectional"))
      (node (ref "U3") (pin "6") (pinfunction "USBD-_6") (pintype "passive"))
    )
    (net (code "42") (name "Net-(J3-DP1)") (class "Default")
      (node (ref "J3") (pin "A6") (pinfunction "DP1_A6") (pintype "bidirectional"))
      (node (ref "J3") (pin "B6") (pinfunction "DP2_B6") (pintype "bidirectional"))
      (node (ref "U3") (pin "5") (pinfunction "USBD+_5") (pintype "passive"))
    )
    (net (code "43") (name "Net-(U2-VIN)") (class "Default")
      (node (ref "C5") (pin "1") (pinfunction "1_1") (pintype "passive"))
      (node (ref "C7") (pin "2") (pinfunction "2_2") (pintype "passive"))
      (node (ref "F1") (pin "2") (pinfunction "2_2") (pintype "passive"))
      (node (ref "U2") (pin "3") (pinfunction "VIN_3") (pintype "passive"))
    )
    (net (code "44") (name "Net-(U3-DTR)") (class "Default")
      (node (ref "C16") (pin "2") (pinfunction "2_2") (pintype "passive"))
      (node (ref "R4") (pin "2") (pinfunction "2_2") (pintype "passive"))
      (node (ref "U3") (pin "13") (pinfunction "DTR_13") (pintype "passive"))
    )
    (net (code "45") (name "Net-(U3-RX)") (class "Default")
      (node (ref "R3") (pin "1") (pinfunction "1_1") (pintype "passive"))
      (node (ref "R6") (pin "1") (pinfunction "1_1") (pintype "passive"))
      (node (ref "U3") (pin "3") (pinfunction "RX_3") (pintype "passive"))
    )
    (net (code "46") (name "Net-(U3-TX)") (class "Default")
      (node (ref "R2") (pin "1") (pinfunction "1_1") (pintype "passive"))
      (node (ref "R5") (pin "1") (pinfunction "1_1") (pintype "passive"))
      (node (ref "U3") (pin "2") (pinfunction "TX_2") (pintype "passive"))
    )
    (net (code "47") (name "Net-(U3-V3)") (class "Default")
      (node (ref "C9") (pin "2") (pinfunction "2_2") (pintype "passive"))
      (node (ref "U3") (pin "4") (pinfunction "V3_4") (pintype "passive"))
    )
    (net (code "48") (name "Net-(U3-XI)") (class "Default")
      (node (ref "C13") (pin "2") (pinfunction "2_2") (pintype "passive"))
      (node (ref "U3") (pin "7") (pinfunction "XI_7") (pintype "passive"))
      (node (ref "X1") (pin "2") (pinfunction "OSC2_2") (pintype "passive"))
    )
    (net (code "49") (name "Net-(U3-XO)") (class "Default")
      (node (ref "C12") (pin "2") (pinfunction "2_2") (pintype "passive"))
      (node (ref "U3") (pin "8") (pinfunction "XO_8") (pintype "passive"))
      (node (ref "X1") (pin "1") (pinfunction "OSC1_1") (pintype "passive"))
    )
    (net (code "50") (name "Net-(U4-VIN)") (class "Default")
      (node (ref "C18") (pin "1") (pinfunction "1_1") (pintype "passive"))
      (node (ref "C20") (pin "2") (pinfunction "2_2") (pintype "passive"))
      (node (ref "F4") (pin "2") (pinfunction "2_2") (pintype "passive"))
      (node (ref "U4") (pin "3") (pinfunction "VIN_3") (pintype "passive"))
    )
    (net (code "51") (name "Vin") (class "Default")
      (node (ref "D1") (pin "1") (pinfunction "ANODE_1") (pintype "passive"))
      (node (ref "F3") (pin "2") (pinfunction "2_2") (pintype "passive"))
      (node (ref "F4") (pin "1") (pinfunction "1_1") (pintype "passive"))
      (node (ref "P1") (pin "POW8") (pinfunction "Vin_POW8") (pintype "passive"))
    )
    (net (code "52") (name "Vusb") (class "Default")
      (node (ref "C10") (pin "1") (pinfunction "1_1") (pintype "passive"))
      (node (ref "C11") (pin "2") (pinfunction "2_2") (pintype "passive"))
      (node (ref "F2") (pin "2") (pinfunction "2_2") (pintype "passive"))
      (node (ref "JP1") (pin "3") (pinfunction "3_3") (pintype "passive"))
      (node (ref "U3") (pin "16") (pinfunction "VCC_16") (pintype "passive"))
    )
    (net (code "53") (name "unconnected-(J1-VCC-Pad2)") (class "Default")
      (node (ref "J1") (pin "2") (pinfunction "VCC_2") (pintype "passive+no_connect"))
    )
    (net (code "54") (name "unconnected-(P1-IOREF-PadPOW2)") (class "Default")
      (node (ref "P1") (pin "POW2") (pinfunction "IOREF_POW2") (pintype "passive+no_connect"))
    )
    (net (code "55") (name "unconnected-(P1-RESV-PadPOW1)") (class "Default")
      (node (ref "P1") (pin "POW1") (pinfunction "RESV_POW1") (pintype "passive+no_connect"))
    )
    (net (code "56") (name "unconnected-(U3-CTS-Pad9)") (class "Default")
      (node (ref "U3") (pin "9") (pinfunction "CTS_9") (pintype "passive+no_connect"))
    )
    (net (code "57") (name "unconnected-(U3-DCD-Pad12)") (class "Default")
      (node (ref "U3") (pin "12") (pinfunction "DCD_12") (pintype "passive+no_connect"))
    )
    (net (code "58") (name "unconnected-(U3-DSR-Pad10)") (class "Default")
      (node (ref "U3") (pin "10") (pinfunction "DSR_10") (pintype "passive+no_connect"))
    )
    (net (code "59") (name "unconnected-(U3-RI-Pad11)") (class "Default")
      (node (ref "U3") (pin "11") (pinfunction "RI_11") (pintype "passive+no_connect"))
    )
    (net (code "60") (name "unconnected-(U3-RS232-Pad15)") (class "Default")
      (node (ref "U3") (pin "15") (pinfunction "RS232_15") (pintype "passive+no_connect"))
    )
    (net (code "61") (name "unconnected-(U3-RTS-Pad14)") (class "Default")
      (node (ref "U3") (pin "14") (pinfunction "RTS_14") (pintype "passive+no_connect"))
    )
  )
)
